# IMU.net
KiCad netlist of a schematic drawn in Altium Designer
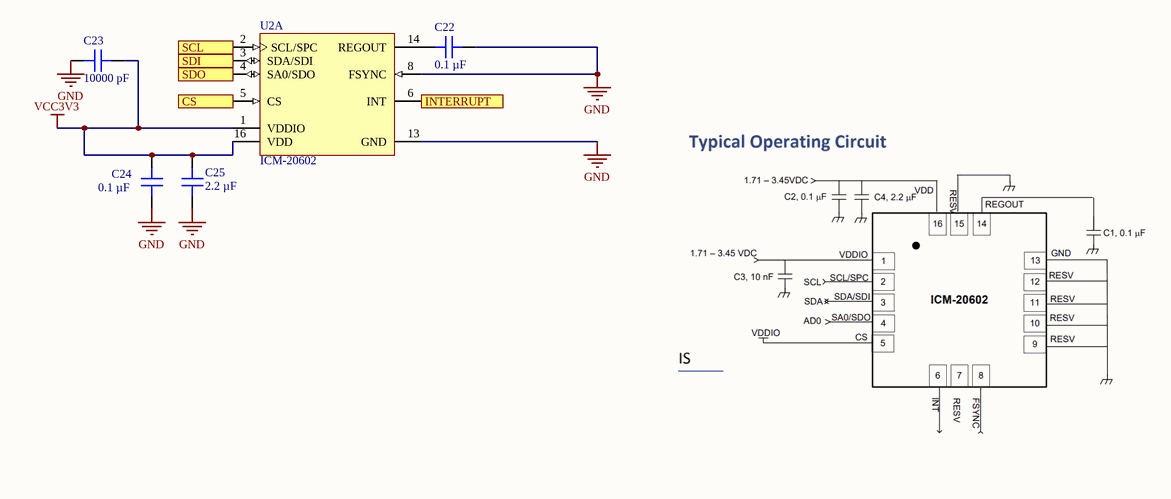
[diagram p0: IMU.SchDoc]

(export (version "E")
  (design (tool "Eeschema 10.0.6"))
  (components
    (comp (ref "C22")
      (value "0.1 µF")
      (footprint "CAP 0603_1608")
      (description "CAP CER 0.1UF 50V X7R 0603")
      (fields (field (name "PART NUMBER") "C0603C104K5RAC7411") (field (name "MANUFACTURER") "KEMET"))
      (libsource (lib "Celestial Altium Library - altium_library") (part "Capacitor"))
    )
    (comp (ref "C23")
      (value "10000 pF")
      (footprint "CAP 0603_1608")
      (description "CAP CER 0603 10NF 16V X7R 10%")
      (fields (field (name "PART NUMBER") "C0603C103K4RECAUTO") (field (name "MANUFACTURER") "KEMET"))
      (libsource (lib "Celestial Altium Library - altium_library") (part "Capacitor"))
    )
    (comp (ref "C24")
      (value "0.1 µF")
      (footprint "CAP 0603_1608")
      (description "CAP CER 0.1UF 50V X7R 0603")
      (fields (field (name "PART NUMBER") "C0603C104K5RAC7411") (field (name "MANUFACTURER") "KEMET"))
      (libsource (lib "Celestial Altium Library - altium_library") (part "Capacitor"))
    )
    (comp (ref "C25")
      (value "2.2 µF")
      (footprint "CAP 0603_1608")
      (description "CAP CER 2.2UF 10V Y5V 0603")
      (fields (field (name "PART NUMBER") "CC0603ZRY5V6BB225") (field (name "MANUFACTURER") "Yageo"))
      (libsource (lib "Celestial Altium Library - altium_library") (part "Capacitor"))
    )
    (comp (ref "U2")
      (value "ICM-20602")
      (footprint "INSE-I62-16")
      (fields (field (name "MANUFACTURER") "InvenSense"))
      (libsource (lib "Altium Content Vault") (part "INSE-ICM-20602-16"))
    )
  )
  (nets
    (net (code "1") (name "/CS") (class "Default")
      (node (ref "U2") (pin "5") (pinfunction "CS_5") (pintype "input"))
    )
    (net (code "2") (name "/INTERRUPT") (class "Default")
      (node (ref "U2") (pin "6") (pinfunction "INT_6") (pintype "open_collector"))
    )
    (net (code "3") (name "/SCL") (class "Default")
      (node (ref "U2") (pin "2") (pinfunction "SCL/SPC_2") (pintype "input"))
    )
    (net (code "4") (name "/SDI") (class "Default")
      (node (ref "U2") (pin "3") (pinfunction "SDA/SDI_3") (pintype "bidirectional"))
    )
    (net (code "5") (name "/SDO") (class "Default")
      (node (ref "U2") (pin "4") (pinfunction "SA0/SDO_4") (pintype "bidirectional"))
    )
    (net (code "6") (name "GND") (class "Default")
      (node (ref "C22") (pin "2") (pinfunction "2_2") (pintype "passive"))
      (node (ref "C23") (pin "1") (pinfunction "1_1") (pintype "passive"))
      (node (ref "C24") (pin "1") (pinfunction "1_1") (pintype "passive"))
      (node (ref "C25") (pin "1") (pinfunction "1_1") (pintype "passive"))
      (node (ref "U2") (pin "13") (pinfunction "GND_13") (pintype "power_in"))
      (node (ref "U2") (pin "8") (pinfunction "FSYNC_8") (pintype "input"))
    )
    (net (code "7") (name "Net-(U2A-REGOUT)") (class "Default")
      (node (ref "C22") (pin "1") (pinfunction "1_1") (pintype "passive"))
      (node (ref "U2") (pin "14") (pinfunction "REGOUT_14") (pintype "passive"))
    )
    (net (code "8") (name "VCC3V3") (class "Default")
      (node (ref "C23") (pin "2") (pinfunction "2_2") (pintype "passive"))
      (node (ref "C24") (pin "2") (pinfunction "2_2") (pintype "passive"))
      (node (ref "C25") (pin "2") (pinfunction "2_2") (pintype "passive"))
      (node (ref "U2") (pin "1") (pinfunction "VDDIO_1") (pintype "power_in"))
      (node (ref "U2") (pin "16") (pinfunction "VDD_16") (pintype "power_in"))
    )
  )
)
